# main_mosfet.net
KiCad netlist of a schematic drawn in EAGLE
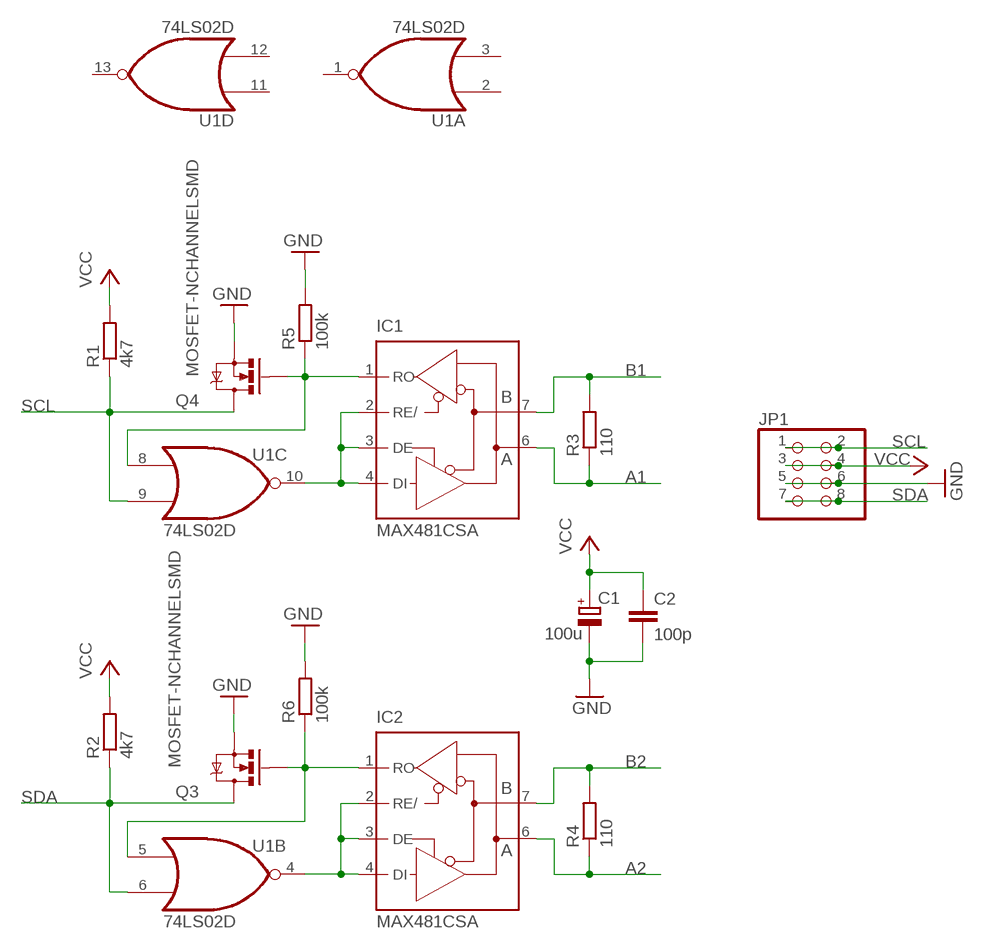
[diagram p0: schematic, sheet 1]

(export (version "E")
  (design (tool "Eeschema 10.0.6"))
  (components
    (comp (ref "C1")
      (value "100u")
      (footprint "eagle-import:E2-4")
      (libsource (lib "eagle-import") (part "CPOL-EUE2-4"))
    )
    (comp (ref "C2")
      (value "100p")
      (footprint "eagle-import:C025-024X044")
      (libsource (lib "eagle-import") (part "C-EU025-024X044"))
    )
    (comp (ref "IC1")
      (value "MAX481CSA")
      (footprint "eagle-import:SO08")
      (libsource (lib "eagle-import") (part "MAX481CSA"))
    )
    (comp (ref "IC2")
      (value "MAX481CSA")
      (footprint "eagle-import:SO08")
      (libsource (lib "eagle-import") (part "MAX481CSA"))
    )
    (comp (ref "JP1")
      (value "PINHD-2X4")
      (footprint "eagle-import:2X04")
      (libsource (lib "eagle-import") (part "PINHD-2X4"))
    )
    (comp (ref "Q3")
      (value "MOSFET-NCHANNELSMD")
      (footprint "eagle-import:SOT23-3")
      (libsource (lib "eagle-import") (part "MOSFET-NCHANNELSMD"))
    )
    (comp (ref "Q4")
      (value "MOSFET-NCHANNELSMD")
      (footprint "eagle-import:SOT23-3")
      (libsource (lib "eagle-import") (part "MOSFET-NCHANNELSMD"))
    )
    (comp (ref "R1")
      (value "4k7")
      (footprint "eagle-import:R0805")
      (libsource (lib "eagle-import") (part "R-EU_R0805"))
    )
    (comp (ref "R2")
      (value "4k7")
      (footprint "eagle-import:R0805")
      (libsource (lib "eagle-import") (part "R-EU_R0805"))
    )
    (comp (ref "R3")
      (value "110")
      (footprint "eagle-import:R0805")
      (libsource (lib "eagle-import") (part "R-EU_R0805"))
    )
    (comp (ref "R4")
      (value "110")
      (footprint "eagle-import:R0805")
      (libsource (lib "eagle-import") (part "R-EU_R0805"))
    )
    (comp (ref "R5")
      (value "100k")
      (footprint "eagle-import:R0805")
      (libsource (lib "eagle-import") (part "R-EU_R0805"))
    )
    (comp (ref "R6")
      (value "100k")
      (footprint "eagle-import:R0805")
      (libsource (lib "eagle-import") (part "R-EU_R0805"))
    )
    (comp (ref "U1")
      (value "74LS02D")
      (footprint "eagle-import:SO14")
      (libsource (lib "eagle-import") (part "7402DLS"))
    )
  )
  (nets
    (net (code "1") (name "/A1") (class "Default")
      (node (ref "IC1") (pin "6") (pinfunction "A_6") (pintype "passive"))
      (node (ref "R3") (pin "1") (pinfunction "1_1") (pintype "passive"))
    )
    (net (code "2") (name "/A2") (class "Default")
      (node (ref "IC2") (pin "6") (pinfunction "A_6") (pintype "passive"))
      (node (ref "R4") (pin "1") (pinfunction "1_1") (pintype "passive"))
    )
    (net (code "3") (name "/B1") (class "Default")
      (node (ref "IC1") (pin "7") (pinfunction "B_7") (pintype "passive"))
      (node (ref "R3") (pin "2") (pinfunction "2_2") (pintype "passive"))
    )
    (net (code "4") (name "/B2") (class "Default")
      (node (ref "IC2") (pin "7") (pinfunction "B_7") (pintype "passive"))
      (node (ref "R4") (pin "2") (pinfunction "2_2") (pintype "passive"))
    )
    (net (code "5") (name "/SCL") (class "Default")
      (node (ref "JP1") (pin "1") (pinfunction "1_1") (pintype "passive"))
      (node (ref "JP1") (pin "2") (pinfunction "2_2") (pintype "passive"))
      (node (ref "Q4") (pin "3") (pinfunction "D_3") (pintype "passive"))
      (node (ref "R1") (pin "1") (pinfunction "1_1") (pintype "passive"))
      (node (ref "U1") (pin "9") (pinfunction "I1_9") (pintype "input"))
    )
    (net (code "6") (name "/SDA") (class "Default")
      (node (ref "JP1") (pin "7") (pinfunction "7_7") (pintype "passive"))
      (node (ref "JP1") (pin "8") (pinfunction "8_8") (pintype "passive"))
      (node (ref "Q3") (pin "3") (pinfunction "D_3") (pintype "passive"))
      (node (ref "R2") (pin "1") (pinfunction "1_1") (pintype "passive"))
      (node (ref "U1") (pin "6") (pinfunction "I1_6") (pintype "input"))
    )
    (net (code "7") (name "GND") (class "Default")
      (node (ref "C1") (pin "-") (pinfunction "-_-") (pintype "passive"))
      (node (ref "C2") (pin "2") (pinfunction "2_2") (pintype "passive"))
      (node (ref "JP1") (pin "5") (pinfunction "5_5") (pintype "passive"))
      (node (ref "JP1") (pin "6") (pinfunction "6_6") (pintype "passive"))
      (node (ref "Q3") (pin "2") (pinfunction "S_2") (pintype "passive"))
      (node (ref "Q4") (pin "2") (pinfunction "S_2") (pintype "passive"))
      (node (ref "R5") (pin "2") (pinfunction "2_2") (pintype "passive"))
      (node (ref "R6") (pin "2") (pinfunction "2_2") (pintype "passive"))
    )
    (net (code "8") (name "Net-(IC1A-DE)") (class "Default")
      (node (ref "IC1") (pin "2") (pinfunction "RE/_2") (pintype "input"))
      (node (ref "IC1") (pin "3") (pinfunction "DE_3") (pintype "input"))
      (node (ref "IC1") (pin "4") (pinfunction "DI_4") (pintype "input"))
      (node (ref "U1") (pin "10") (pinfunction "O_10") (pintype "output"))
    )
    (net (code "9") (name "Net-(IC1A-RO)") (class "Default")
      (node (ref "IC1") (pin "1") (pinfunction "RO_1") (pintype "output"))
      (node (ref "Q4") (pin "1") (pinfunction "G_1") (pintype "passive"))
      (node (ref "R5") (pin "1") (pinfunction "1_1") (pintype "passive"))
      (node (ref "U1") (pin "8") (pinfunction "I0_8") (pintype "input"))
    )
    (net (code "10") (name "Net-(IC2A-DE)") (class "Default")
      (node (ref "IC2") (pin "2") (pinfunction "RE/_2") (pintype "input"))
      (node (ref "IC2") (pin "3") (pinfunction "DE_3") (pintype "input"))
      (node (ref "IC2") (pin "4") (pinfunction "DI_4") (pintype "input"))
      (node (ref "U1") (pin "4") (pinfunction "O_4") (pintype "output"))
    )
    (net (code "11") (name "Net-(IC2A-RO)") (class "Default")
      (node (ref "IC2") (pin "1") (pinfunction "RO_1") (pintype "output"))
      (node (ref "Q3") (pin "1") (pinfunction "G_1") (pintype "passive"))
      (node (ref "R6") (pin "1") (pinfunction "1_1") (pintype "passive"))
      (node (ref "U1") (pin "5") (pinfunction "I0_5") (pintype "input"))
    )
    (net (code "12") (name "VCC") (class "Default")
      (node (ref "C1") (pin "+") (pinfunction "+_+") (pintype "passive"))
      (node (ref "C2") (pin "1") (pinfunction "1_1") (pintype "passive"))
      (node (ref "JP1") (pin "3") (pinfunction "3_3") (pintype "passive"))
      (node (ref "JP1") (pin "4") (pinfunction "4_4") (pintype "passive"))
      (node (ref "R1") (pin "2") (pinfunction "2_2") (pintype "passive"))
      (node (ref "R2") (pin "2") (pinfunction "2_2") (pintype "passive"))
    )
    (net (code "13") (name "unconnected-(U1A-I0-Pad2)") (class "Default")
      (node (ref "U1") (pin "2") (pinfunction "I0_2") (pintype "input"))
    )
    (net (code "14") (name "unconnected-(U1A-I1-Pad3)") (class "Default")
      (node (ref "U1") (pin "3") (pinfunction "I1_3") (pintype "input"))
    )
    (net (code "15") (name "unconnected-(U1A-O-Pad1)") (class "Default")
      (node (ref "U1") (pin "1") (pinfunction "O_1") (pintype "output"))
    )
    (net (code "16") (name "unconnected-(U1D-I0-Pad11)") (class "Default")
      (node (ref "U1") (pin "11") (pinfunction "I0_11") (pintype "input"))
    )
    (net (code "17") (name "unconnected-(U1D-I1-Pad12)") (class "Default")
      (node (ref "U1") (pin "12") (pinfunction "I1_12") (pintype "input"))
    )
    (net (code "18") (name "unconnected-(U1D-O-Pad13)") (class "Default")
      (node (ref "U1") (pin "13") (pinfunction "O_13") (pintype "output"))
    )
  )
)
